# 30-172_-_SM_Clock_Ethernet_Module.net
KiCad netlist of a schematic drawn in Altium Designer
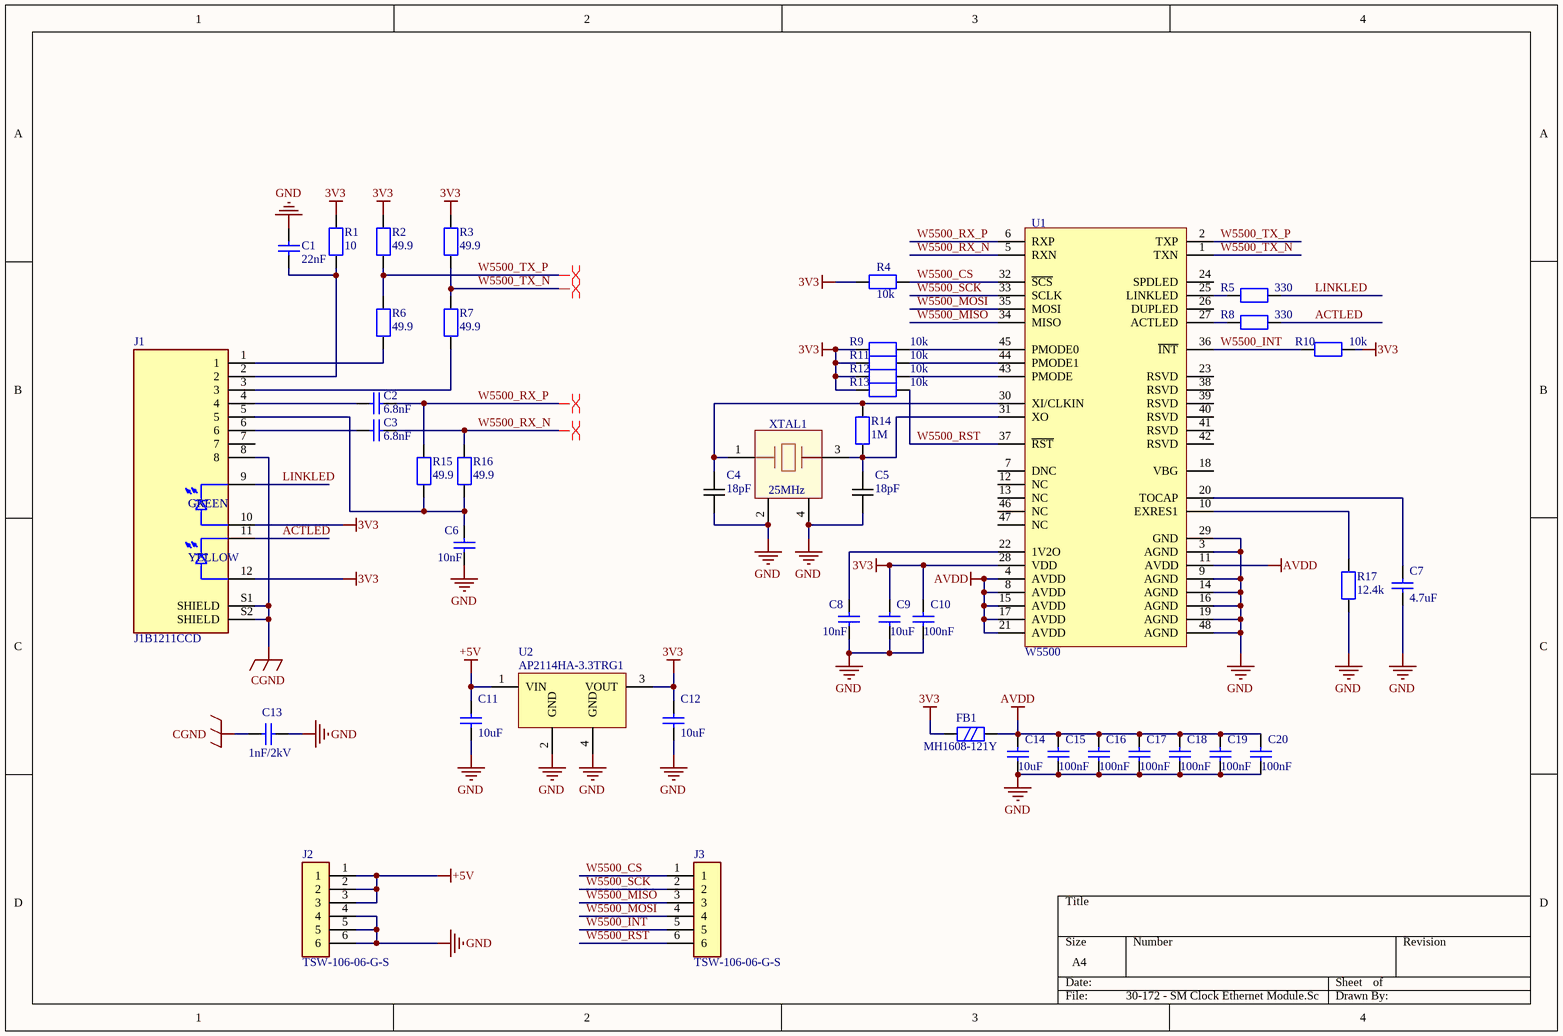
[diagram p0: 30-172 - SM Clock Ethernet Module.SchDoc]

(export (version "E")
  (design (tool "Eeschema 10.0.6"))
  (components
    (comp (ref "C1")
      (value "22nF")
      (footprint "C0603")
      (description "22nF ± 10% 50V")
      (fields
        (field (name "MANUFACTURER") "Yageo")
        (field (name "MANUFACTURER PART NUMBER") "CC0603KRX7R9BB223")
      )
      (libsource (lib "SM Desk Clock-Timer") (part "22nF ± 10% 50V"))
    )
    (comp (ref "C2")
      (value "6.8nF")
      (footprint "C0603")
      (description "6.8nF ± 10% 50V")
      (fields
        (field (name "MANUFACTURER") "Yageo")
        (field (name "MANUFACTURER PART NUMBER") "CC0603KPX7R9BB682")
      )
      (libsource (lib "SM Desk Clock-Timer") (part "6.8nF ± 10% 50V"))
    )
    (comp (ref "C3")
      (value "6.8nF")
      (footprint "C0603")
      (description "6.8nF ± 10% 50V")
      (fields
        (field (name "MANUFACTURER") "Yageo")
        (field (name "MANUFACTURER PART NUMBER") "CC0603KPX7R9BB682")
      )
      (libsource (lib "SM Desk Clock-Timer") (part "6.8nF ± 10% 50V"))
    )
    (comp (ref "C4")
      (value "18pF")
      (footprint "C0603")
      (description "18pF 50V 0603 X7R")
      (fields
        (field (name "MANUFACTURER") "Yageo")
        (field (name "MANUFACTURER PART NUMBER") "CC0603FRNPO9BN180")
      )
      (libsource (lib "32-503 - DriveHUB - 1Ch 10A Variable CV") (part "18pF 50V 0603 X7R"))
    )
    (comp (ref "C5")
      (value "18pF")
      (footprint "C0603")
      (description "18pF 50V 0603 X7R")
      (fields
        (field (name "MANUFACTURER") "Yageo")
        (field (name "MANUFACTURER PART NUMBER") "CC0603FRNPO9BN180")
      )
      (libsource (lib "32-503 - DriveHUB - 1Ch 10A Variable CV") (part "18pF 50V 0603 X7R"))
    )
    (comp (ref "C6")
      (value "10nF")
      (footprint "C0603")
      (description "10nF ± 10% 50V")
      (fields
        (field (name "MANUFACTURER") "Yageo")
        (field (name "MANUFACTURER PART NUMBER") "CC0603KRX7R9BB103")
      )
      (libsource (lib "SM Desk Clock-Timer") (part "10nF ± 10% 50V"))
    )
    (comp (ref "C7")
      (value "4.7uF")
      (footprint "C0805")
      (description "4.7uF ± 10% 25V")
      (fields
        (field (name "MANUFACTURER") "Yageo")
        (field (name "MANUFACTURER PART NUMBER") "CC0805KKX7R8BB475")
      )
      (libsource (lib "SM Desk Clock-Timer") (part "4.7uF ± 10% 25V"))
    )
    (comp (ref "C8")
      (value "10nF")
      (footprint "C0603")
      (description "10nF ± 10% 50V")
      (fields
        (field (name "MANUFACTURER") "Yageo")
        (field (name "MANUFACTURER PART NUMBER") "CC0603KRX7R9BB103")
      )
      (libsource (lib "SM Desk Clock-Timer") (part "10nF ± 10% 50V"))
    )
    (comp (ref "C9")
      (value "10uF")
      (footprint "C0805")
      (description "10uF ± 10% 16V")
      (fields
        (field (name "MANUFACTURER") "Yageo")
        (field (name "MANUFACTURER PART NUMBER") "CC0805KKX5R7BB106")
      )
      (libsource (lib "SM Desk Clock-Timer") (part "10uF ± 10% 16V"))
    )
    (comp (ref "C10")
      (value "100nF")
      (footprint "C0603")
      (description "100nF ± 10% 50V")
      (fields
        (field (name "MANUFACTURER") "Yageo")
        (field (name "MANUFACTURER PART NUMBER") "CC0603KRX7R9BB104")
      )
      (libsource (lib "Cue Light Output PCB - RJ45") (part "100nF ± 10% 50V"))
    )
    (comp (ref "C11")
      (value "10uF")
      (footprint "C0805")
      (description "10uF ± 10% 16V")
      (fields
        (field (name "MANUFACTURER") "Yageo")
        (field (name "MANUFACTURER PART NUMBER") "CC0805KKX5R7BB106")
      )
      (libsource (lib "SM Desk Clock-Timer") (part "10uF ± 10% 16V"))
    )
    (comp (ref "C12")
      (value "10uF")
      (footprint "C0805")
      (description "10uF ± 10% 16V")
      (fields
        (field (name "MANUFACTURER") "Yageo")
        (field (name "MANUFACTURER PART NUMBER") "CC0805KKX5R7BB106")
      )
      (libsource (lib "SM Desk Clock-Timer") (part "10uF ± 10% 16V"))
    )
    (comp (ref "C13")
      (value "1nF/2kV")
      (footprint "C1206")
      (description "1nF ± 10% 2kV")
      (fields
        (field (name "MANUFACTURER") "Yageo")
        (field (name "MANUFACTURER PART NUMBER") "CC1206KKX7RDBB102")
      )
      (libsource (lib "SM Desk Clock-Timer") (part "1nF ± 10% 2kV"))
    )
    (comp (ref "C14")
      (value "10uF")
      (footprint "C0805")
      (description "10uF ± 10% 16V")
      (fields
        (field (name "MANUFACTURER") "Yageo")
        (field (name "MANUFACTURER PART NUMBER") "CC0805KKX5R7BB106")
      )
      (libsource (lib "SM Desk Clock-Timer") (part "10uF ± 10% 16V"))
    )
    (comp (ref "C15")
      (value "100nF")
      (footprint "C0603")
      (description "100nF ± 10% 50V")
      (fields
        (field (name "MANUFACTURER") "Yageo")
        (field (name "MANUFACTURER PART NUMBER") "CC0603KRX7R9BB104")
      )
      (libsource (lib "Cue Light Output PCB - RJ45") (part "100nF ± 10% 50V"))
    )
    (comp (ref "C16")
      (value "100nF")
      (footprint "C0603")
      (description "100nF ± 10% 50V")
      (fields
        (field (name "MANUFACTURER") "Yageo")
        (field (name "MANUFACTURER PART NUMBER") "CC0603KRX7R9BB104")
      )
      (libsource (lib "Cue Light Output PCB - RJ45") (part "100nF ± 10% 50V"))
    )
    (comp (ref "C17")
      (value "100nF")
      (footprint "C0603")
      (description "100nF ± 10% 50V")
      (fields
        (field (name "MANUFACTURER") "Yageo")
        (field (name "MANUFACTURER PART NUMBER") "CC0603KRX7R9BB104")
      )
      (libsource (lib "Cue Light Output PCB - RJ45") (part "100nF ± 10% 50V"))
    )
    (comp (ref "C18")
      (value "100nF")
      (footprint "C0603")
      (description "100nF ± 10% 50V")
      (fields
        (field (name "MANUFACTURER") "Yageo")
        (field (name "MANUFACTURER PART NUMBER") "CC0603KRX7R9BB104")
      )
      (libsource (lib "Cue Light Output PCB - RJ45") (part "100nF ± 10% 50V"))
    )
    (comp (ref "C19")
      (value "100nF")
      (footprint "C0603")
      (description "100nF ± 10% 50V")
      (fields
        (field (name "MANUFACTURER") "Yageo")
        (field (name "MANUFACTURER PART NUMBER") "CC0603KRX7R9BB104")
      )
      (libsource (lib "Cue Light Output PCB - RJ45") (part "100nF ± 10% 50V"))
    )
    (comp (ref "C20")
      (value "100nF")
      (footprint "C0603")
      (description "100nF ± 10% 50V")
      (fields
        (field (name "MANUFACTURER") "Yageo")
        (field (name "MANUFACTURER PART NUMBER") "CC0603KRX7R9BB104")
      )
      (libsource (lib "Cue Light Output PCB - RJ45") (part "100nF ± 10% 50V"))
    )
    (comp (ref "FB1")
      (value "MH1608-121Y")
      (footprint "L0603")
      (description "Ferrite Beads 120 ohms 25% HIGH CURRENT")
      (fields (field (name "MANUFACTURER") "Bourns"))
      (libsource (lib "SM Desk Clock-Timer") (part "MH1608-121Y"))
    )
    (comp (ref "J1")
      (value "J1B1211CCD")
      (footprint "J1B1211CCD")
      (description "Modular Connectors / Ethernet Connectors RJ-45 w/ Transformer Connector /CETUS")
      (fields (field (name "MANUFACTURER") "WIZnet"))
      (libsource (lib "30-172 - SM Clock Ethernet Module") (part "J1B1211CCD"))
    )
    (comp (ref "J2")
      (value "TSW-106-06-G-S")
      (footprint "TSW-106-06-G-S")
      (description "Headers & Wire Housings Classic PCB Header Strips, 0.100\" pitch")
      (fields (field (name "MANUFACTURER") "Samtec"))
      (libsource (lib "") (part "TSW-106-06-G-S_1"))
    )
    (comp (ref "J3")
      (value "TSW-106-06-G-S")
      (footprint "TSW-106-06-G-S")
      (description "Headers & Wire Housings Classic PCB Header Strips, 0.100\" pitch")
      (fields (field (name "MANUFACTURER") "Samtec"))
      (libsource (lib "SM Desk Clock-Timer") (part "TSW-106-06-G-S"))
    )
    (comp (ref "R1")
      (value "10")
      (footprint "R0603")
      (description "10 Ohms ±1% 0.1W")
      (fields
        (field (name "MANUFACTURER") "Yageo")
        (field (name "MANUFACTURER PART NUMBER") "RC0603FR-0710RL")
      )
      (libsource (lib "SM Desk Clock-Timer") (part "10 Ohms ±1% 0.1W"))
    )
    (comp (ref "R2")
      (value "49.9")
      (footprint "R0603")
      (description "49.9 Ohms ±1% 0.1W")
      (fields
        (field (name "MANUFACTURER") "Yageo")
        (field (name "MANUFACTURER PART NUMBER") "RC0603FR-0749R9L")
      )
      (libsource (lib "SM Desk Clock-Timer") (part "49.9 Ohms ±1% 0.1W"))
    )
    (comp (ref "R3")
      (value "49.9")
      (footprint "R0603")
      (description "49.9 Ohms ±1% 0.1W")
      (fields
        (field (name "MANUFACTURER") "Yageo")
        (field (name "MANUFACTURER PART NUMBER") "RC0603FR-0749R9L")
      )
      (libsource (lib "SM Desk Clock-Timer") (part "49.9 Ohms ±1% 0.1W"))
    )
    (comp (ref "R4")
      (value "10k")
      (footprint "R0603")
      (description "10 kOhms ±1% 0.1W")
      (fields
        (field (name "MANUFACTURER") "Yageo")
        (field (name "MANUFACTURER PART NUMBER") "RC0603FR-0710KL")
      )
      (libsource (lib "SM Desk Clock-Timer") (part "10 kOhms ±1% 0.1W"))
    )
    (comp (ref "R5")
      (value "330")
      (footprint "R0603")
      (description "330 Ohms ±1% 0.1W")
      (fields
        (field (name "MANUFACTURER") "Yageo")
        (field (name "MANUFACTURER PART NUMBER") "RC0603FR-07330RL")
      )
      (libsource (lib "SM Desk Clock-Timer") (part "330 Ohms ±1% 0.1W"))
    )
    (comp (ref "R6")
      (value "49.9")
      (footprint "R0603")
      (description "49.9 Ohms ±1% 0.1W")
      (fields
        (field (name "MANUFACTURER") "Yageo")
        (field (name "MANUFACTURER PART NUMBER") "RC0603FR-0749R9L")
      )
      (libsource (lib "SM Desk Clock-Timer") (part "49.9 Ohms ±1% 0.1W"))
    )
    (comp (ref "R7")
      (value "49.9")
      (footprint "R0603")
      (description "49.9 Ohms ±1% 0.1W")
      (fields
        (field (name "MANUFACTURER") "Yageo")
        (field (name "MANUFACTURER PART NUMBER") "RC0603FR-0749R9L")
      )
      (libsource (lib "SM Desk Clock-Timer") (part "49.9 Ohms ±1% 0.1W"))
    )
    (comp (ref "R8")
      (value "330")
      (footprint "R0603")
      (description "330 Ohms ±1% 0.1W")
      (fields
        (field (name "MANUFACTURER") "Yageo")
        (field (name "MANUFACTURER PART NUMBER") "RC0603FR-07330RL")
      )
      (libsource (lib "SM Desk Clock-Timer") (part "330 Ohms ±1% 0.1W"))
    )
    (comp (ref "R9")
      (value "10k")
      (footprint "R0603")
      (description "10 kOhms ±1% 0.1W")
      (fields
        (field (name "MANUFACTURER") "Yageo")
        (field (name "MANUFACTURER PART NUMBER") "RC0603FR-0710KL")
      )
      (libsource (lib "SM Desk Clock-Timer") (part "10 kOhms ±1% 0.1W"))
    )
    (comp (ref "R10")
      (value "10k")
      (footprint "R0603")
      (description "10 kOhms ±1% 0.1W")
      (fields
        (field (name "MANUFACTURER") "Yageo")
        (field (name "MANUFACTURER PART NUMBER") "RC0603FR-0710KL")
      )
      (libsource (lib "SM Desk Clock-Timer") (part "10 kOhms ±1% 0.1W"))
    )
    (comp (ref "R11")
      (value "10k")
      (footprint "R0603")
      (description "10 kOhms ±1% 0.1W")
      (fields
        (field (name "MANUFACTURER") "Yageo")
        (field (name "MANUFACTURER PART NUMBER") "RC0603FR-0710KL")
      )
      (libsource (lib "SM Desk Clock-Timer") (part "10 kOhms ±1% 0.1W"))
    )
    (comp (ref "R12")
      (value "10k")
      (footprint "R0603")
      (description "10 kOhms ±1% 0.1W")
      (fields
        (field (name "MANUFACTURER") "Yageo")
        (field (name "MANUFACTURER PART NUMBER") "RC0603FR-0710KL")
      )
      (libsource (lib "SM Desk Clock-Timer") (part "10 kOhms ±1% 0.1W"))
    )
    (comp (ref "R13")
      (value "10k")
      (footprint "R0603")
      (description "10 kOhms ±1% 0.1W")
      (fields
        (field (name "MANUFACTURER") "Yageo")
        (field (name "MANUFACTURER PART NUMBER") "RC0603FR-0710KL")
      )
      (libsource (lib "SM Desk Clock-Timer") (part "10 kOhms ±1% 0.1W"))
    )
    (comp (ref "R14")
      (value "1M")
      (footprint "R0603")
      (description "1 MOhms ±1% 0.1W")
      (fields
        (field (name "MANUFACTURER") "Yageo")
        (field (name "MANUFACTURER PART NUMBER") "RC0603FR-071ML")
      )
      (libsource (lib "SM Desk Clock-Timer") (part "1 MOhms ±1% 0.1W"))
    )
    (comp (ref "R15")
      (value "49.9")
      (footprint "R0603")
      (description "49.9 Ohms ±1% 0.1W")
      (fields
        (field (name "MANUFACTURER") "Yageo")
        (field (name "MANUFACTURER PART NUMBER") "RC0603FR-0749R9L")
      )
      (libsource (lib "SM Desk Clock-Timer") (part "49.9 Ohms ±1% 0.1W"))
    )
    (comp (ref "R16")
      (value "49.9")
      (footprint "R0603")
      (description "49.9 Ohms ±1% 0.1W")
      (fields
        (field (name "MANUFACTURER") "Yageo")
        (field (name "MANUFACTURER PART NUMBER") "RC0603FR-0749R9L")
      )
      (libsource (lib "SM Desk Clock-Timer") (part "49.9 Ohms ±1% 0.1W"))
    )
    (comp (ref "R17")
      (value "12.4k")
      (footprint "R0603")
      (description "12.4 kOhms ±1% 0.1W")
      (fields
        (field (name "MANUFACTURER") "Yageo")
        (field (name "MANUFACTURER PART NUMBER") "RC0603FR-0712K4L")
      )
      (libsource (lib "SM Desk Clock-Timer_1") (part "12.4 kOhms ±1% 0.1W"))
    )
    (comp (ref "U1")
      (value "W5500")
      (footprint "LQFP-48")
      (description "Ethernet ICs 3in1 Enet Controller TCP/IP +MAC+PHY")
      (fields (field (name "MANUFACTURER") "WIZnet"))
      (libsource (lib "SM Desk Clock-Timer_1") (part "W5500"))
    )
    (comp (ref "U2")
      (value "AP2114HA-3.3TRG1")
      (footprint "SOT223-3")
      (description "LDO Voltage Regulators 1A LN CMOS LDO 0.45V 60uA 50mA")
      (fields (field (name "MANUFACTURER") "Diodes Inc."))
      (libsource (lib "SM Desk Clock-Timer") (part "AP2114HA-3.3TRG1"))
    )
    (comp (ref "XTAL1")
      (value "25MHz")
      (footprint "ECS2501836B2CTYTR")
      (fields
        (field (name "MANUFACTURER") "ECS")
        (field (name "MANUFACTURER PART NUMBER") "ECS-250-18-36B2-CTY-TR")
      )
      (libsource (lib "SM Desk Clock-Timer_1") (part "ECS-250-18-36B2-CTY-TR"))
    )
  )
  (nets
    (net (code "1") (name "+5V") (class "Default")
      (node (ref "C11") (pin "2") (pinfunction "2_2") (pintype "passive"))
      (node (ref "J2") (pin "1") (pinfunction "1_1") (pintype "passive"))
      (node (ref "J2") (pin "2") (pinfunction "2_2") (pintype "passive"))
      (node (ref "J2") (pin "3") (pinfunction "3_3") (pintype "passive"))
      (node (ref "U2") (pin "1") (pinfunction "VIN_1") (pintype "passive"))
    )
    (net (code "2") (name "/ACTLED") (class "Default")
      (node (ref "J1") (pin "11") (pinfunction "11_11") (pintype "passive"))
      (node (ref "R8") (pin "2") (pinfunction "2_2") (pintype "passive"))
    )
    (net (code "3") (name "/LINKLED") (class "Default")
      (node (ref "J1") (pin "9") (pinfunction "9_9") (pintype "passive"))
      (node (ref "R5") (pin "2") (pinfunction "2_2") (pintype "passive"))
    )
    (net (code "4") (name "/W5500_CS") (class "Default")
      (node (ref "J3") (pin "1") (pinfunction "1_1") (pintype "passive"))
      (node (ref "R4") (pin "1") (pinfunction "1_1") (pintype "passive"))
      (node (ref "U1") (pin "32") (pinfunction "~{SCS}_32") (pintype "passive"))
    )
    (net (code "5") (name "/W5500_INT") (class "Default")
      (node (ref "J3") (pin "5") (pinfunction "5_5") (pintype "passive"))
      (node (ref "R10") (pin "1") (pinfunction "1_1") (pintype "passive"))
      (node (ref "U1") (pin "36") (pinfunction "~{INT}_36") (pintype "passive"))
    )
    (net (code "6") (name "/W5500_MISO") (class "Default")
      (node (ref "J3") (pin "3") (pinfunction "3_3") (pintype "passive"))
      (node (ref "U1") (pin "34") (pinfunction "MISO_34") (pintype "passive"))
    )
    (net (code "7") (name "/W5500_MOSI") (class "Default")
      (node (ref "J3") (pin "4") (pinfunction "4_4") (pintype "passive"))
      (node (ref "U1") (pin "35") (pinfunction "MOSI_35") (pintype "passive"))
    )
    (net (code "8") (name "/W5500_RST") (class "Default")
      (node (ref "J3") (pin "6") (pinfunction "6_6") (pintype "passive"))
      (node (ref "R13") (pin "1") (pinfunction "1_1") (pintype "passive"))
      (node (ref "U1") (pin "37") (pinfunction "~{RST}_37") (pintype "passive"))
    )
    (net (code "9") (name "/W5500_RX_N") (class "Default")
      (node (ref "C3") (pin "2") (pinfunction "2_2") (pintype "passive"))
      (node (ref "R16") (pin "2") (pinfunction "2_2") (pintype "passive"))
      (node (ref "U1") (pin "5") (pinfunction "RXN_5") (pintype "passive"))
    )
    (net (code "10") (name "/W5500_RX_P") (class "Default")
      (node (ref "C2") (pin "2") (pinfunction "2_2") (pintype "passive"))
      (node (ref "R15") (pin "2") (pinfunction "2_2") (pintype "passive"))
      (node (ref "U1") (pin "6") (pinfunction "RXP_6") (pintype "passive"))
    )
    (net (code "11") (name "/W5500_SCK") (class "Default")
      (node (ref "J3") (pin "2") (pinfunction "2_2") (pintype "passive"))
      (node (ref "U1") (pin "33") (pinfunction "SCLK_33") (pintype "passive"))
    )
    (net (code "12") (name "/W5500_TX_N") (class "Default")
      (node (ref "R3") (pin "1") (pinfunction "1_1") (pintype "passive"))
      (node (ref "R7") (pin "2") (pinfunction "2_2") (pintype "passive"))
      (node (ref "U1") (pin "1") (pinfunction "TXN_1") (pintype "passive"))
    )
    (net (code "13") (name "/W5500_TX_P") (class "Default")
      (node (ref "R2") (pin "1") (pinfunction "1_1") (pintype "passive"))
      (node (ref "R6") (pin "2") (pinfunction "2_2") (pintype "passive"))
      (node (ref "U1") (pin "2") (pinfunction "TXP_2") (pintype "passive"))
    )
    (net (code "14") (name "3V3") (class "Default")
      (node (ref "C10") (pin "2") (pinfunction "2_2") (pintype "passive"))
      (node (ref "C12") (pin "2") (pinfunction "2_2") (pintype "passive"))
      (node (ref "C9") (pin "2") (pinfunction "2_2") (pintype "passive"))
      (node (ref "FB1") (pin "1") (pinfunction "1_1") (pintype "passive"))
      (node (ref "J1") (pin "10") (pinfunction "10_10") (pintype "passive"))
      (node (ref "J1") (pin "12") (pinfunction "12_12") (pintype "passive"))
      (node (ref "R1") (pin "2") (pinfunction "2_2") (pintype "passive"))
      (node (ref "R10") (pin "2") (pinfunction "2_2") (pintype "passive"))
      (node (ref "R11") (pin "2") (pinfunction "2_2") (pintype "passive"))
      (node (ref "R12") (pin "2") (pinfunction "2_2") (pintype "passive"))
      (node (ref "R13") (pin "2") (pinfunction "2_2") (pintype "passive"))
      (node (ref "R2") (pin "2") (pinfunction "2_2") (pintype "passive"))
      (node (ref "R3") (pin "2") (pinfunction "2_2") (pintype "passive"))
      (node (ref "R4") (pin "2") (pinfunction "2_2") (pintype "passive"))
      (node (ref "R9") (pin "2") (pinfunction "2_2") (pintype "passive"))
      (node (ref "U1") (pin "28") (pinfunction "VDD_28") (pintype "passive"))
      (node (ref "U2") (pin "3") (pinfunction "VOUT_3") (pintype "passive"))
    )
    (net (code "15") (name "AVDD") (class "Default")
      (node (ref "C14") (pin "2") (pinfunction "2_2") (pintype "passive"))
      (node (ref "C15") (pin "2") (pinfunction "2_2") (pintype "passive"))
      (node (ref "C16") (pin "2") (pinfunction "2_2") (pintype "passive"))
      (node (ref "C17") (pin "2") (pinfunction "2_2") (pintype "passive"))
      (node (ref "C18") (pin "2") (pinfunction "2_2") (pintype "passive"))
      (node (ref "C19") (pin "2") (pinfunction "2_2") (pintype "passive"))
      (node (ref "C20") (pin "2") (pinfunction "2_2") (pintype "passive"))
      (node (ref "FB1") (pin "2") (pinfunction "2_2") (pintype "passive"))
      (node (ref "U1") (pin "11") (pinfunction "AVDD_11") (pintype "passive"))
      (node (ref "U1") (pin "15") (pinfunction "AVDD_15") (pintype "passive"))
      (node (ref "U1") (pin "17") (pinfunction "AVDD_17") (pintype "passive"))
      (node (ref "U1") (pin "21") (pinfunction "AVDD_21") (pintype "passive"))
      (node (ref "U1") (pin "4") (pinfunction "AVDD_4") (pintype "passive"))
      (node (ref "U1") (pin "8") (pinfunction "AVDD_8") (pintype "passive"))
    )
    (net (code "16") (name "CGND") (class "Default")
      (node (ref "C13") (pin "1") (pinfunction "1_1") (pintype "passive"))
      (node (ref "J1") (pin "8") (pinfunction "8_8") (pintype "passive"))
      (node (ref "J1") (pin "S1") (pinfunction "SHIELD_S1") (pintype "passive"))
      (node (ref "J1") (pin "S2") (pinfunction "SHIELD_S2") (pintype "passive"))
    )
    (net (code "17") (name "GND") (class "Default")
      (node (ref "C1") (pin "2") (pinfunction "2_2") (pintype "passive"))
      (node (ref "C10") (pin "1") (pinfunction "1_1") (pintype "passive"))
      (node (ref "C11") (pin "1") (pinfunction "1_1") (pintype "passive"))
      (node (ref "C12") (pin "1") (pinfunction "1_1") (pintype "passive"))
      (node (ref "C13") (pin "2") (pinfunction "2_2") (pintype "passive"))
      (node (ref "C14") (pin "1") (pinfunction "1_1") (pintype "passive"))
      (node (ref "C15") (pin "1") (pinfunction "1_1") (pintype "passive"))
      (node (ref "C16") (pin "1") (pinfunction "1_1") (pintype "passive"))
      (node (ref "C17") (pin "1") (pinfunction "1_1") (pintype "passive"))
      (node (ref "C18") (pin "1") (pinfunction "1_1") (pintype "passive"))
      (node (ref "C19") (pin "1") (pinfunction "1_1") (pintype "passive"))
      (node (ref "C20") (pin "1") (pinfunction "1_1") (pintype "passive"))
      (node (ref "C4") (pin "1") (pinfunction "1_1") (pintype "passive"))
      (node (ref "C5") (pin "1") (pinfunction "1_1") (pintype "passive"))
      (node (ref "C6") (pin "1") (pinfunction "1_1") (pintype "passive"))
      (node (ref "C7") (pin "1") (pinfunction "1_1") (pintype "passive"))
      (node (ref "C8") (pin "1") (pinfunction "1_1") (pintype "passive"))
      (node (ref "C9") (pin "1") (pinfunction "1_1") (pintype "passive"))
      (node (ref "J2") (pin "4") (pinfunction "4_4") (pintype "passive"))
      (node (ref "J2") (pin "5") (pinfunction "5_5") (pintype "passive"))
      (node (ref "J2") (pin "6") (pinfunction "6_6") (pintype "passive"))
      (node (ref "R17") (pin "1") (pinfunction "1_1") (pintype "passive"))
      (node (ref "U1") (pin "14") (pinfunction "AGND_14") (pintype "passive"))
      (node (ref "U1") (pin "16") (pinfunction "AGND_16") (pintype "passive"))
      (node (ref "U1") (pin "19") (pinfunction "AGND_19") (pintype "passive"))
      (node (ref "U1") (pin "29") (pinfunction "GND_29") (pintype "passive"))
      (node (ref "U1") (pin "3") (pinfunction "AGND_3") (pintype "passive"))
      (node (ref "U1") (pin "48") (pinfunction "AGND_48") (pintype "passive"))
      (node (ref "U1") (pin "9") (pinfunction "AGND_9") (pintype "passive"))
      (node (ref "U2") (pin "2") (pinfunction "GND_2") (pintype "passive"))
      (node (ref "U2") (pin "4") (pinfunction "GND_4") (pintype "passive"))
      (node (ref "XTAL1") (pin "2") (pinfunction "2_2") (pintype "passive"))
      (node (ref "XTAL1") (pin "4") (pinfunction "4_4") (pintype "passive"))
    )
    (net (code "18") (name "Net-(C1-Pad1)") (class "Default")
      (node (ref "C1") (pin "1") (pinfunction "1_1") (pintype "passive"))
      (node (ref "J1") (pin "2") (pinfunction "2_2") (pintype "passive"))
      (node (ref "R1") (pin "1") (pinfunction "1_1") (pintype "passive"))
    )
    (net (code "19") (name "Net-(C2-Pad1)") (class "Default")
      (node (ref "C2") (pin "1") (pinfunction "1_1") (pintype "passive"))
      (node (ref "J1") (pin "4") (pinfunction "4_4") (pintype "passive"))
    )
    (net (code "20") (name "Net-(C3-Pad1)") (class "Default")
      (node (ref "C3") (pin "1") (pinfunction "1_1") (pintype "passive"))
      (node (ref "J1") (pin "6") (pinfunction "6_6") (pintype "passive"))
    )
    (net (code "21") (name "Net-(C6-Pad2)") (class "Default")
      (node (ref "C6") (pin "2") (pinfunction "2_2") (pintype "passive"))
      (node (ref "J1") (pin "5") (pinfunction "5_5") (pintype "passive"))
      (node (ref "R15") (pin "1") (pinfunction "1_1") (pintype "passive"))
      (node (ref "R16") (pin "1") (pinfunction "1_1") (pintype "passive"))
    )
    (net (code "22") (name "Net-(J1-Pad1)") (class "Default")
      (node (ref "J1") (pin "1") (pinfunction "1_1") (pintype "passive"))
      (node (ref "R6") (pin "1") (pinfunction "1_1") (pintype "passive"))
    )
    (net (code "23") (name "Net-(J1-Pad3)") (class "Default")
      (node (ref "J1") (pin "3") (pinfunction "3_3") (pintype "passive"))
      (node (ref "R7") (pin "1") (pinfunction "1_1") (pintype "passive"))
    )
    (net (code "24") (name "Net-(U1-1V2O)") (class "Default")
      (node (ref "C8") (pin "2") (pinfunction "2_2") (pintype "passive"))
      (node (ref "U1") (pin "22") (pinfunction "1V2O_22") (pintype "passive"))
    )
    (net (code "25") (name "Net-(U1-ACTLED)") (class "Default")
      (node (ref "R8") (pin "1") (pinfunction "1_1") (pintype "passive"))
      (node (ref "U1") (pin "27") (pinfunction "ACTLED_27") (pintype "passive"))
    )
    (net (code "26") (name "Net-(U1-EXRES1)") (class "Default")
      (node (ref "R17") (pin "2") (pinfunction "2_2") (pintype "passive"))
      (node (ref "U1") (pin "10") (pinfunction "EXRES1_10") (pintype "passive"))
    )
    (net (code "27") (name "Net-(U1-LINKLED)") (class "Default")
      (node (ref "R5") (pin "1") (pinfunction "1_1") (pintype "passive"))
      (node (ref "U1") (pin "25") (pinfunction "LINKLED_25") (pintype "passive"))
    )
    (net (code "28") (name "Net-(U1-PMODE)") (class "Default")
      (node (ref "R12") (pin "1") (pinfunction "1_1") (pintype "passive"))
      (node (ref "U1") (pin "43") (pinfunction "PMODE_43") (pintype "passive"))
    )
    (net (code "29") (name "Net-(U1-PMODE0)") (class "Default")
      (node (ref "R9") (pin "1") (pinfunction "1_1") (pintype "passive"))
      (node (ref "U1") (pin "45") (pinfunction "PMODE0_45") (pintype "passive"))
    )
    (net (code "30") (name "Net-(U1-PMODE1)") (class "Default")
      (node (ref "R11") (pin "1") (pinfunction "1_1") (pintype "passive"))
      (node (ref "U1") (pin "44") (pinfunction "PMODE1_44") (pintype "passive"))
    )
    (net (code "31") (name "Net-(U1-TOCAP)") (class "Default")
      (node (ref "C7") (pin "2") (pinfunction "2_2") (pintype "passive"))
      (node (ref "U1") (pin "20") (pinfunction "TOCAP_20") (pintype "passive"))
    )
    (net (code "32") (name "Net-(U1-XI{slash}CLKIN)") (class "Default")
      (node (ref "C4") (pin "2") (pinfunction "2_2") (pintype "passive"))
      (node (ref "R14") (pin "2") (pinfunction "2_2") (pintype "passive"))
      (node (ref "U1") (pin "30") (pinfunction "XI/CLKIN_30") (pintype "passive"))
      (node (ref "XTAL1") (pin "1") (pinfunction "1_1") (pintype "passive"))
    )
    (net (code "33") (name "Net-(U1-XO)") (class "Default")
      (node (ref "C5") (pin "2") (pinfunction "2_2") (pintype "passive"))
      (node (ref "R14") (pin "1") (pinfunction "1_1") (pintype "passive"))
      (node (ref "U1") (pin "31") (pinfunction "XO_31") (pintype "passive"))
      (node (ref "XTAL1") (pin "3") (pinfunction "3_3") (pintype "passive"))
    )
    (net (code "34") (name "unconnected-(J1-Pad7)") (class "Default")
      (node (ref "J1") (pin "7") (pinfunction "7_7") (pintype "passive"))
    )
    (net (code "35") (name "unconnected-(U1-DNC-Pad7)") (class "Default")
      (node (ref "U1") (pin "7") (pinfunction "DNC_7") (pintype "passive"))
    )
    (net (code "36") (name "unconnected-(U1-DUPLED-Pad26)") (class "Default")
      (node (ref "U1") (pin "26") (pinfunction "DUPLED_26") (pintype "passive"))
    )
    (net (code "37") (name "unconnected-(U1-NC-Pad12)") (class "Default")
      (node (ref "U1") (pin "12") (pinfunction "NC_12") (pintype "passive"))
    )
    (net (code "38") (name "unconnected-(U1-NC-Pad13)") (class "Default")
      (node (ref "U1") (pin "13") (pinfunction "NC_13") (pintype "passive"))
    )
    (net (code "39") (name "unconnected-(U1-NC-Pad46)") (class "Default")
      (node (ref "U1") (pin "46") (pinfunction "NC_46") (pintype "passive"))
    )
    (net (code "40") (name "unconnected-(U1-NC-Pad47)") (class "Default")
      (node (ref "U1") (pin "47") (pinfunction "NC_47") (pintype "passive"))
    )
    (net (code "41") (name "unconnected-(U1-RSVD-Pad23)") (class "Default")
      (node (ref "U1") (pin "23") (pinfunction "RSVD_23") (pintype "passive"))
    )
    (net (code "42") (name "unconnected-(U1-RSVD-Pad38)") (class "Default")
      (node (ref "U1") (pin "38") (pinfunction "RSVD_38") (pintype "passive"))
    )
    (net (code "43") (name "unconnected-(U1-RSVD-Pad39)") (class "Default")
      (node (ref "U1") (pin "39") (pinfunction "RSVD_39") (pintype "passive"))
    )
    (net (code "44") (name "unconnected-(U1-RSVD-Pad40)") (class "Default")
      (node (ref "U1") (pin "40") (pinfunction "RSVD_40") (pintype "passive"))
    )
    (net (code "45") (name "unconnected-(U1-RSVD-Pad41)") (class "Default")
      (node (ref "U1") (pin "41") (pinfunction "RSVD_41") (pintype "passive"))
    )
    (net (code "46") (name "unconnected-(U1-RSVD-Pad42)") (class "Default")
      (node (ref "U1") (pin "42") (pinfunction "RSVD_42") (pintype "passive"))
    )
    (net (code "47") (name "unconnected-(U1-SPDLED-Pad24)") (class "Default")
      (node (ref "U1") (pin "24") (pinfunction "SPDLED_24") (pintype "passive"))
    )
    (net (code "48") (name "unconnected-(U1-VBG-Pad18)") (class "Default")
      (node (ref "U1") (pin "18") (pinfunction "VBG_18") (pintype "passive"))
    )
  )
)
